# internal_env_board.net
KiCad netlist of a schematic drawn in EAGLE
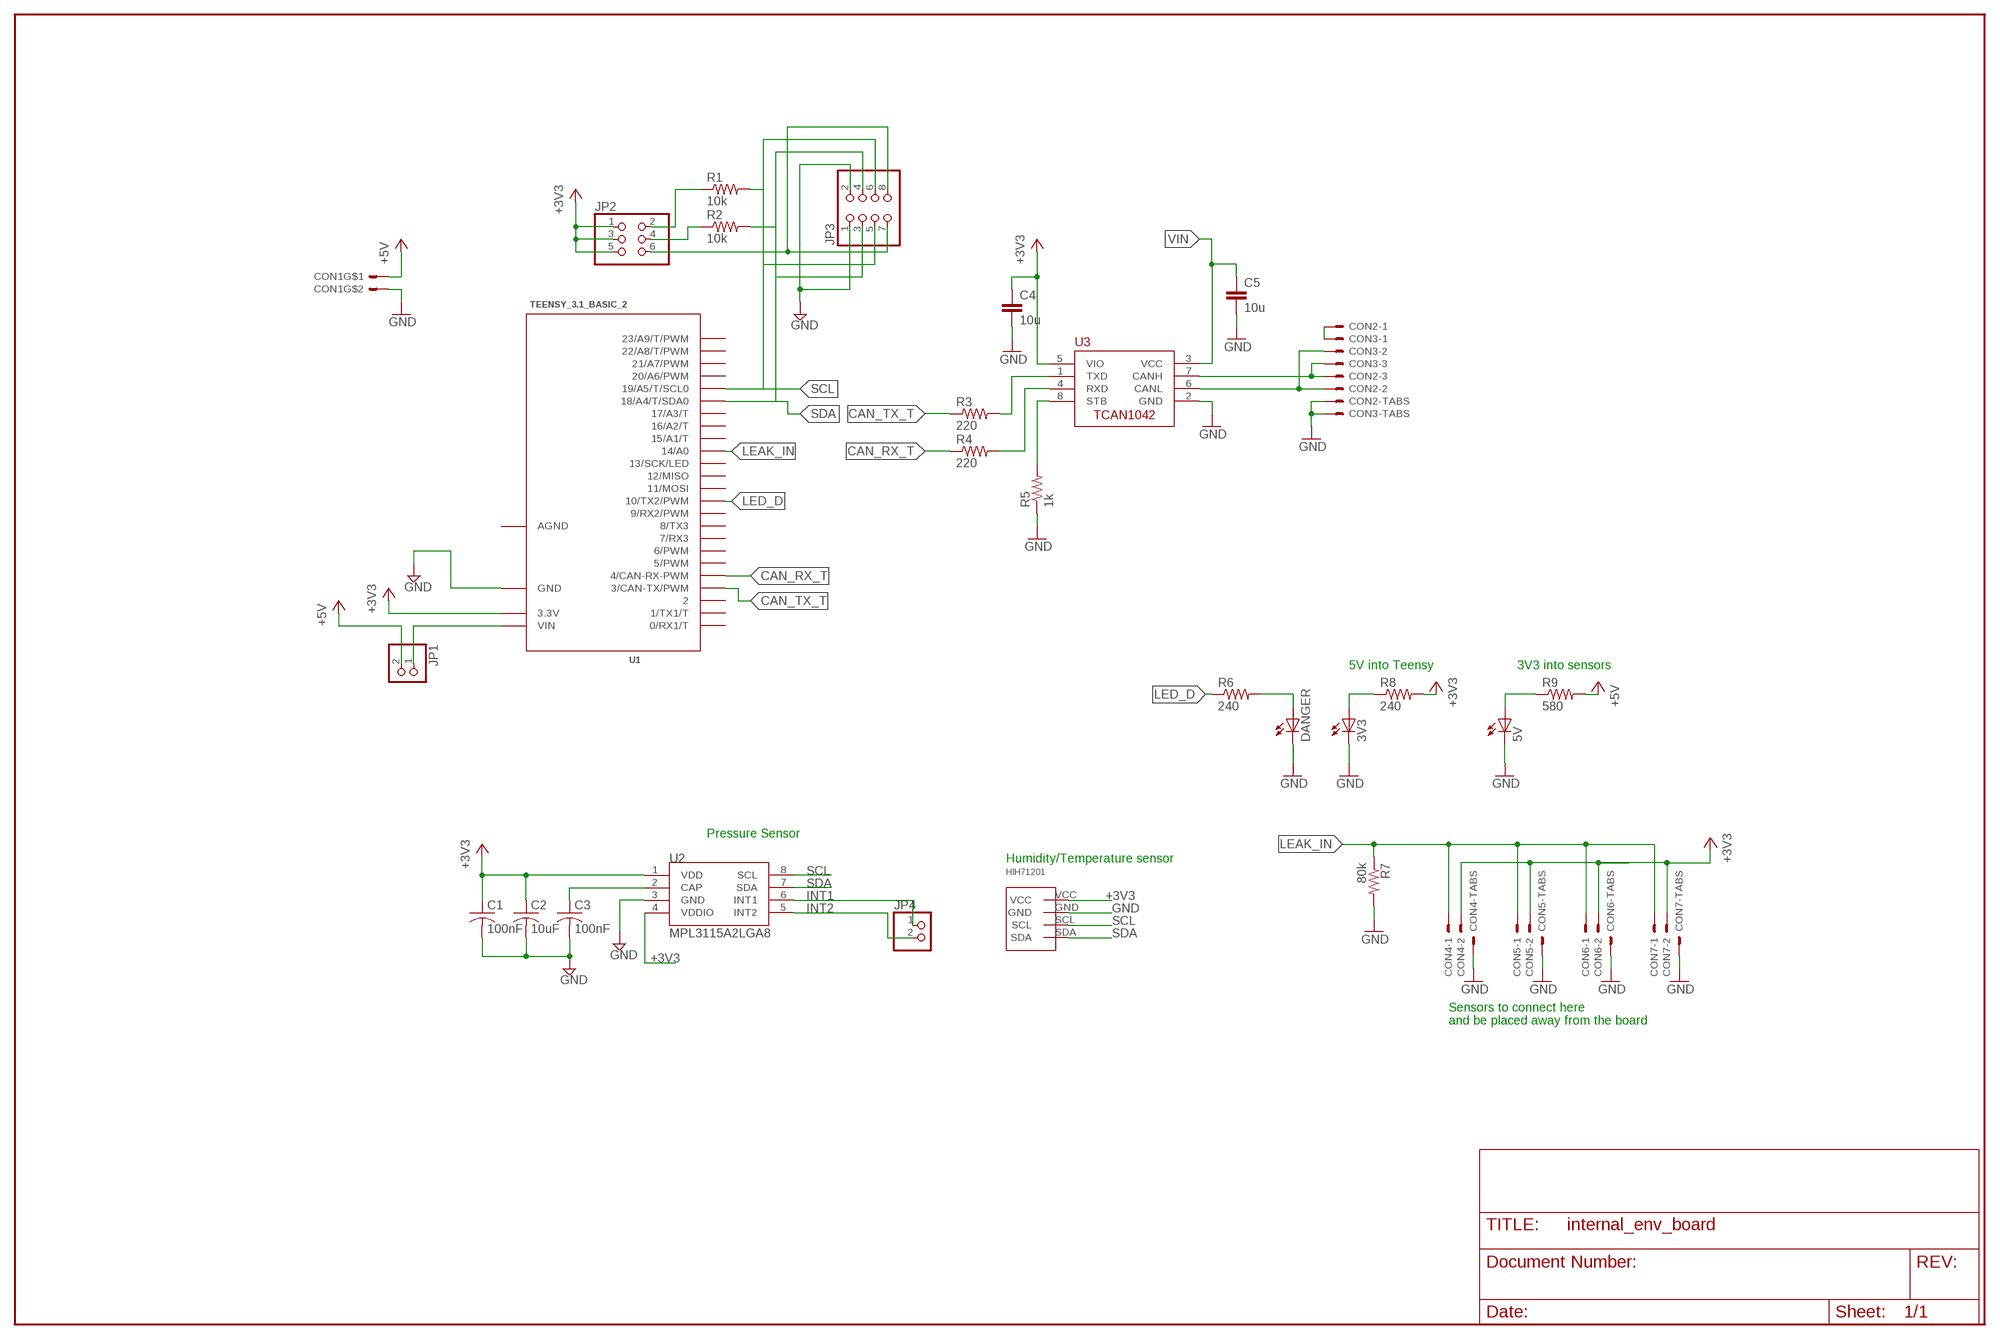
[diagram p0: schematic, sheet 1]

(export (version "E")
  (design (tool "Eeschema 10.0.6"))
  (components
    (comp (ref "3V3")
      (value "LEDSMT1206")
      (footprint "eagle-import:1206")
      (libsource (lib "eagle-import") (part "LEDSMT1206"))
    )
    (comp (ref "5V")
      (value "LEDSMT1206")
      (footprint "eagle-import:1206")
      (libsource (lib "eagle-import") (part "LEDSMT1206"))
    )
    (comp (ref "C1")
      (value "100nF")
      (footprint "eagle-import:C1206")
      (libsource (lib "eagle-import") (part "C-USC1206"))
    )
    (comp (ref "C2")
      (value "10uF")
      (footprint "eagle-import:C1206")
      (libsource (lib "eagle-import") (part "C-USC1206"))
    )
    (comp (ref "C3")
      (value "100nF")
      (footprint "eagle-import:C1206")
      (libsource (lib "eagle-import") (part "C-USC1206"))
    )
    (comp (ref "C4")
      (value "10u")
      (footprint "eagle-import:C0805")
      (libsource (lib "eagle-import") (part "C-EUC0805"))
    )
    (comp (ref "C5")
      (value "10u")
      (footprint "eagle-import:C0805")
      (libsource (lib "eagle-import") (part "C-EUC0805"))
    )
    (comp (ref "CON1")
      (value "MOLEX_5566-2")
      (footprint "eagle-import:5566-2")
      (libsource (lib "eagle-import") (part "MOLEX_5566-2"))
    )
    (comp (ref "CON2")
      (value "SM03B-GHS-TB")
      (footprint "eagle-import:SM03B-GHS-TB")
      (libsource (lib "eagle-import") (part "SM03B-GHS-TB"))
    )
    (comp (ref "CON3")
      (value "SM03B-GHS-TB")
      (footprint "eagle-import:SM03B-GHS-TB")
      (libsource (lib "eagle-import") (part "SM03B-GHS-TB"))
    )
    (comp (ref "CON4")
      (value "SM02B-GHS-TB")
      (footprint "eagle-import:SM02B-GHS-TB")
      (libsource (lib "eagle-import") (part "SM02B-GHS-TB"))
    )
    (comp (ref "CON5")
      (value "SM02B-GHS-TB")
      (footprint "eagle-import:SM02B-GHS-TB")
      (libsource (lib "eagle-import") (part "SM02B-GHS-TB"))
    )
    (comp (ref "CON6")
      (value "SM02B-GHS-TB")
      (footprint "eagle-import:SM02B-GHS-TB")
      (libsource (lib "eagle-import") (part "SM02B-GHS-TB"))
    )
    (comp (ref "CON7")
      (value "SM02B-GHS-TB")
      (footprint "eagle-import:SM02B-GHS-TB")
      (libsource (lib "eagle-import") (part "SM02B-GHS-TB"))
    )
    (comp (ref "DANGER")
      (value "LEDSMT1206")
      (footprint "eagle-import:1206")
      (libsource (lib "eagle-import") (part "LEDSMT1206"))
    )
    (comp (ref "HIH71201")
      (value "HIH7120")
      (footprint "eagle-import:SIP4")
      (libsource (lib "eagle-import") (part "HIH7120"))
    )
    (comp (ref "JP1")
      (value "PINHD-1X2")
      (footprint "eagle-import:1X02")
      (libsource (lib "eagle-import") (part "pinhead_325_PINHD-1X2"))
    )
    (comp (ref "JP2")
      (value "PINHD-2X3")
      (footprint "eagle-import:2X03")
      (libsource (lib "eagle-import") (part "PINHD-2X3"))
    )
    (comp (ref "JP3")
      (value "PINHD-2X4")
      (footprint "eagle-import:2X04")
      (libsource (lib "eagle-import") (part "PINHD-2X4"))
    )
    (comp (ref "JP4")
      (value "PINHD-1X2")
      (footprint "eagle-import:1X02")
      (libsource (lib "eagle-import") (part "PINHD-1X2"))
    )
    (comp (ref "R1")
      (value "10k")
      (footprint "eagle-import:R1206")
      (libsource (lib "eagle-import") (part "R-US_R1206"))
    )
    (comp (ref "R2")
      (value "10k")
      (footprint "eagle-import:R1206")
      (libsource (lib "eagle-import") (part "R-US_R1206"))
    )
    (comp (ref "R3")
      (value "220")
      (footprint "eagle-import:R0805")
      (libsource (lib "eagle-import") (part "R-US_R0805"))
    )
    (comp (ref "R4")
      (value "220")
      (footprint "eagle-import:R0805")
      (libsource (lib "eagle-import") (part "R-US_R0805"))
    )
    (comp (ref "R5")
      (value "1k")
      (footprint "eagle-import:R0805")
      (libsource (lib "eagle-import") (part "R-US_R0805"))
    )
    (comp (ref "R6")
      (value "240")
      (footprint "eagle-import:R1206")
      (libsource (lib "eagle-import") (part "resistor_348_R-US_R1206"))
    )
    (comp (ref "R7")
      (value "80k")
      (footprint "eagle-import:R1206")
      (libsource (lib "eagle-import") (part "resistor_348_R-US_R1206"))
    )
    (comp (ref "R8")
      (value "240")
      (footprint "eagle-import:R1206")
      (libsource (lib "eagle-import") (part "resistor_348_R-US_R1206"))
    )
    (comp (ref "R9")
      (value "580")
      (footprint "eagle-import:R1206")
      (libsource (lib "eagle-import") (part "resistor_348_R-US_R1206"))
    )
    (comp (ref "U1")
      (value "TEENSY_3.1_BASIC_2")
      (footprint "eagle-import:TEENSY_3.1_BASIC_2")
      (libsource (lib "eagle-import") (part "TEENSY_3.1_BASIC_2"))
    )
    (comp (ref "U2")
      (value "MPL3115A2LGA8")
      (footprint "eagle-import:LGA8")
      (libsource (lib "eagle-import") (part "MPL3115A2LGA8"))
    )
    (comp (ref "U3")
      (value "TCAN1042HVDR")
      (footprint "eagle-import:SO-8")
      (libsource (lib "eagle-import") (part "TCAN1042HVDR"))
    )
  )
  (nets
    (net (code "1") (name "+3V3") (class "Default")
      (node (ref "C1") (pin "1") (pinfunction "1_1") (pintype "passive"))
      (node (ref "C2") (pin "1") (pinfunction "1_1") (pintype "passive"))
      (node (ref "C4") (pin "1") (pinfunction "1_1") (pintype "passive"))
      (node (ref "CON4") (pin "P$2") (pinfunction "S_P$2") (pintype "passive"))
      (node (ref "CON5") (pin "P$2") (pinfunction "S_P$2") (pintype "passive"))
      (node (ref "CON6") (pin "P$2") (pinfunction "S_P$2") (pintype "passive"))
      (node (ref "CON7") (pin "P$2") (pinfunction "S_P$2") (pintype "passive"))
      (node (ref "HIH71201") (pin "VCC") (pinfunction "VCC_VCC") (pintype "power_in"))
      (node (ref "JP2") (pin "1") (pinfunction "1_1") (pintype "passive"))
      (node (ref "JP2") (pin "3") (pinfunction "3_3") (pintype "passive"))
      (node (ref "JP2") (pin "5") (pinfunction "5_5") (pintype "passive"))
      (node (ref "R8") (pin "2") (pinfunction "2_2") (pintype "passive"))
      (node (ref "U1") (pin "3.3V") (pinfunction "3.3V_3.3V") (pintype "power_in"))
      (node (ref "U2") (pin "1") (pinfunction "VDD_1") (pintype "bidirectional"))
      (node (ref "U2") (pin "4") (pinfunction "VDDIO_4") (pintype "bidirectional"))
      (node (ref "U3") (pin "5") (pinfunction "VIO_5") (pintype "bidirectional"))
    )
    (net (code "2") (name "+5V") (class "Default")
      (node (ref "CON1") (pin "1") (pinfunction "S_1") (pintype "passive"))
      (node (ref "JP1") (pin "2") (pinfunction "2_2") (pintype "passive"))
      (node (ref "R9") (pin "2") (pinfunction "2_2") (pintype "passive"))
    )
    (net (code "3") (name "/AGND") (class "Default")
      (node (ref "U1") (pin "AGND") (pinfunction "AGND_AGND") (pintype "power_in"))
    )
    (net (code "4") (name "/INT1") (class "Default")
      (node (ref "JP4") (pin "1") (pinfunction "1_1") (pintype "passive"))
      (node (ref "U2") (pin "6") (pinfunction "INT1_6") (pintype "bidirectional"))
    )
    (net (code "5") (name "/INT2") (class "Default")
      (node (ref "JP4") (pin "2") (pinfunction "2_2") (pintype "passive"))
      (node (ref "U2") (pin "5") (pinfunction "INT2_5") (pintype "bidirectional"))
    )
    (net (code "6") (name "CAN_RX_T") (class "Default")
      (node (ref "R4") (pin "1") (pinfunction "1_1") (pintype "passive"))
      (node (ref "U1") (pin "4") (pinfunction "4/CAN-RX-PWM_4") (pintype "bidirectional"))
    )
    (net (code "7") (name "CAN_TX_T") (class "Default")
      (node (ref "R3") (pin "1") (pinfunction "1_1") (pintype "passive"))
      (node (ref "U1") (pin "3") (pinfunction "3/CAN-TX/PWM_3") (pintype "bidirectional"))
    )
    (net (code "8") (name "GND") (class "Default")
      (node (ref "3V3") (pin "C") (pinfunction "C_C") (pintype "passive"))
      (node (ref "5V") (pin "C") (pinfunction "C_C") (pintype "passive"))
      (node (ref "C1") (pin "2") (pinfunction "2_2") (pintype "passive"))
      (node (ref "C2") (pin "2") (pinfunction "2_2") (pintype "passive"))
      (node (ref "C3") (pin "2") (pinfunction "2_2") (pintype "passive"))
      (node (ref "C4") (pin "2") (pinfunction "2_2") (pintype "passive"))
      (node (ref "C5") (pin "2") (pinfunction "2_2") (pintype "passive"))
      (node (ref "CON1") (pin "2") (pinfunction "S_2") (pintype "passive"))
      (node (ref "CON2") (pin "P$4") (pinfunction "S_P$4") (pintype "passive"))
      (node (ref "CON2") (pin "P$5") (pinfunction "S_P$5") (pintype "passive"))
      (node (ref "CON3") (pin "P$4") (pinfunction "S_P$4") (pintype "passive"))
      (node (ref "CON3") (pin "P$5") (pinfunction "S_P$5") (pintype "passive"))
      (node (ref "CON4") (pin "P$3") (pinfunction "S_P$3") (pintype "passive"))
      (node (ref "CON4") (pin "P$4") (pinfunction "S_P$4") (pintype "passive"))
      (node (ref "CON5") (pin "P$3") (pinfunction "S_P$3") (pintype "passive"))
      (node (ref "CON5") (pin "P$4") (pinfunction "S_P$4") (pintype "passive"))
      (node (ref "CON6") (pin "P$3") (pinfunction "S_P$3") (pintype "passive"))
      (node (ref "CON6") (pin "P$4") (pinfunction "S_P$4") (pintype "passive"))
      (node (ref "CON7") (pin "P$3") (pinfunction "S_P$3") (pintype "passive"))
      (node (ref "CON7") (pin "P$4") (pinfunction "S_P$4") (pintype "passive"))
      (node (ref "DANGER") (pin "C") (pinfunction "C_C") (pintype "passive"))
      (node (ref "HIH71201") (pin "GND") (pinfunction "GND_GND") (pintype "power_in"))
      (node (ref "JP3") (pin "1") (pinfunction "1_1") (pintype "passive"))
      (node (ref "JP3") (pin "2") (pinfunction "2_2") (pintype "passive"))
      (node (ref "R5") (pin "1") (pinfunction "1_1") (pintype "passive"))
      (node (ref "R7") (pin "2") (pinfunction "2_2") (pintype "passive"))
      (node (ref "U1") (pin "GND") (pinfunction "GND_GND") (pintype "power_in"))
      (node (ref "U2") (pin "3") (pinfunction "GND_3") (pintype "bidirectional"))
      (node (ref "U3") (pin "2") (pinfunction "GND_2") (pintype "bidirectional"))
    )
    (net (code "9") (name "LEAK_IN") (class "Default")
      (node (ref "CON4") (pin "P$1") (pinfunction "S_P$1") (pintype "passive"))
      (node (ref "CON5") (pin "P$1") (pinfunction "S_P$1") (pintype "passive"))
      (node (ref "CON6") (pin "P$1") (pinfunction "S_P$1") (pintype "passive"))
      (node (ref "CON7") (pin "P$1") (pinfunction "S_P$1") (pintype "passive"))
      (node (ref "R7") (pin "1") (pinfunction "1_1") (pintype "passive"))
      (node (ref "U1") (pin "14/A0") (pinfunction "14/A0_14/A0") (pintype "bidirectional"))
    )
    (net (code "10") (name "LED_D") (class "Default")
      (node (ref "R6") (pin "1") (pinfunction "1_1") (pintype "passive"))
      (node (ref "U1") (pin "10") (pinfunction "10/TX2/PWM_10") (pintype "bidirectional"))
    )
    (net (code "11") (name "Net-(3V3-PadA)") (class "Default")
      (node (ref "3V3") (pin "A") (pinfunction "A_A") (pintype "passive"))
      (node (ref "R8") (pin "1") (pinfunction "1_1") (pintype "passive"))
    )
    (net (code "12") (name "Net-(5V-PadA)") (class "Default")
      (node (ref "5V") (pin "A") (pinfunction "A_A") (pintype "passive"))
      (node (ref "R9") (pin "1") (pinfunction "1_1") (pintype "passive"))
    )
    (net (code "13") (name "Net-(CON2A-S)") (class "Default")
      (node (ref "CON2") (pin "P$1") (pinfunction "S_P$1") (pintype "passive"))
      (node (ref "CON3") (pin "P$1") (pinfunction "S_P$1") (pintype "passive"))
    )
    (net (code "14") (name "Net-(CON2B-S)") (class "Default")
      (node (ref "CON2") (pin "P$2") (pinfunction "S_P$2") (pintype "passive"))
      (node (ref "CON3") (pin "P$2") (pinfunction "S_P$2") (pintype "passive"))
      (node (ref "U3") (pin "6") (pinfunction "CANL_6") (pintype "bidirectional"))
    )
    (net (code "15") (name "Net-(CON2C-S)") (class "Default")
      (node (ref "CON2") (pin "P$3") (pinfunction "S_P$3") (pintype "passive"))
      (node (ref "CON3") (pin "P$3") (pinfunction "S_P$3") (pintype "passive"))
      (node (ref "U3") (pin "7") (pinfunction "CANH_7") (pintype "bidirectional"))
    )
    (net (code "16") (name "Net-(DANGER-PadA)") (class "Default")
      (node (ref "DANGER") (pin "A") (pinfunction "A_A") (pintype "passive"))
      (node (ref "R6") (pin "2") (pinfunction "2_2") (pintype "passive"))
    )
    (net (code "17") (name "Net-(JP2-Pad2)") (class "Default")
      (node (ref "JP2") (pin "2") (pinfunction "2_2") (pintype "passive"))
      (node (ref "R1") (pin "1") (pinfunction "1_1") (pintype "passive"))
    )
    (net (code "18") (name "Net-(JP2-Pad4)") (class "Default")
      (node (ref "JP2") (pin "4") (pinfunction "4_4") (pintype "passive"))
      (node (ref "R2") (pin "1") (pinfunction "1_1") (pintype "passive"))
    )
    (net (code "19") (name "Net-(JP2-Pad6)") (class "Default")
      (node (ref "JP2") (pin "6") (pinfunction "6_6") (pintype "passive"))
      (node (ref "JP3") (pin "7") (pinfunction "7_7") (pintype "passive"))
      (node (ref "JP3") (pin "8") (pinfunction "8_8") (pintype "passive"))
    )
    (net (code "20") (name "Net-(U2-CAP)") (class "Default")
      (node (ref "C3") (pin "1") (pinfunction "1_1") (pintype "passive"))
      (node (ref "U2") (pin "2") (pinfunction "CAP_2") (pintype "bidirectional"))
    )
    (net (code "21") (name "Net-(U3-RXD)") (class "Default")
      (node (ref "R4") (pin "2") (pinfunction "2_2") (pintype "passive"))
      (node (ref "U3") (pin "4") (pinfunction "RXD_4") (pintype "bidirectional"))
    )
    (net (code "22") (name "Net-(U3-STB)") (class "Default")
      (node (ref "R5") (pin "2") (pinfunction "2_2") (pintype "passive"))
      (node (ref "U3") (pin "8") (pinfunction "STB_8") (pintype "bidirectional"))
    )
    (net (code "23") (name "Net-(U3-TXD)") (class "Default")
      (node (ref "R3") (pin "2") (pinfunction "2_2") (pintype "passive"))
      (node (ref "U3") (pin "1") (pinfunction "TXD_1") (pintype "bidirectional"))
    )
    (net (code "24") (name "SCL") (class "Default")
      (node (ref "HIH71201") (pin "SCL") (pinfunction "SCL_SCL") (pintype "bidirectional"))
      (node (ref "JP3") (pin "5") (pinfunction "5_5") (pintype "passive"))
      (node (ref "JP3") (pin "6") (pinfunction "6_6") (pintype "passive"))
      (node (ref "R1") (pin "2") (pinfunction "2_2") (pintype "passive"))
      (node (ref "U1") (pin "19/A5") (pinfunction "19/A5/T/SCL0_19/A5") (pintype "bidirectional"))
      (node (ref "U2") (pin "8") (pinfunction "SCL_8") (pintype "bidirectional"))
    )
    (net (code "25") (name "SDA") (class "Default")
      (node (ref "HIH71201") (pin "SDA") (pinfunction "SDA_SDA") (pintype "bidirectional"))
      (node (ref "JP3") (pin "3") (pinfunction "3_3") (pintype "passive"))
      (node (ref "JP3") (pin "4") (pinfunction "4_4") (pintype "passive"))
      (node (ref "R2") (pin "2") (pinfunction "2_2") (pintype "passive"))
      (node (ref "U1") (pin "18/A4") (pinfunction "18/A4/T/SDA0_18/A4") (pintype "bidirectional"))
      (node (ref "U2") (pin "7") (pinfunction "SDA_7") (pintype "bidirectional"))
    )
    (net (code "26") (name "VIN") (class "Default")
      (node (ref "C5") (pin "1") (pinfunction "1_1") (pintype "passive"))
      (node (ref "JP1") (pin "1") (pinfunction "1_1") (pintype "passive"))
      (node (ref "U1") (pin "VIN") (pinfunction "VIN_VIN") (pintype "power_in"))
      (node (ref "U3") (pin "3") (pinfunction "VCC_3") (pintype "bidirectional"))
    )
    (net (code "27") (name "unconnected-(U1-0{slash}RX1{slash}T-Pad0)") (class "Default")
      (node (ref "U1") (pin "0") (pinfunction "0/RX1/T_0") (pintype "bidirectional"))
    )
    (net (code "28") (name "unconnected-(U1-1{slash}TX1{slash}T-Pad1)") (class "Default")
      (node (ref "U1") (pin "1") (pinfunction "1/TX1/T_1") (pintype "bidirectional"))
    )
    (net (code "29") (name "unconnected-(U1-5{slash}PWM-Pad5)") (class "Default")
      (node (ref "U1") (pin "5") (pinfunction "5/PWM_5") (pintype "bidirectional"))
    )
    (net (code "30") (name "unconnected-(U1-6{slash}PWM-Pad6)") (class "Default")
      (node (ref "U1") (pin "6") (pinfunction "6/PWM_6") (pintype "bidirectional"))
    )
    (net (code "31") (name "unconnected-(U1-7{slash}RX3-Pad7)") (class "Default")
      (node (ref "U1") (pin "7") (pinfunction "7/RX3_7") (pintype "bidirectional"))
    )
    (net (code "32") (name "unconnected-(U1-8{slash}TX3-Pad8)") (class "Default")
      (node (ref "U1") (pin "8") (pinfunction "8/TX3_8") (pintype "bidirectional"))
    )
    (net (code "33") (name "unconnected-(U1-9{slash}RX2{slash}PWM-Pad9)") (class "Default")
      (node (ref "U1") (pin "9") (pinfunction "9/RX2/PWM_9") (pintype "bidirectional"))
    )
    (net (code "34") (name "unconnected-(U1-11{slash}MOSI-Pad11)") (class "Default")
      (node (ref "U1") (pin "11") (pinfunction "11/MOSI_11") (pintype "bidirectional"))
    )
    (net (code "35") (name "unconnected-(U1-12{slash}MISO-Pad12)") (class "Default")
      (node (ref "U1") (pin "12") (pinfunction "12/MISO_12") (pintype "bidirectional"))
    )
    (net (code "36") (name "unconnected-(U1-13{slash}SCK{slash}LED-Pad13)") (class "Default")
      (node (ref "U1") (pin "13") (pinfunction "13/SCK/LED_13") (pintype "bidirectional"))
    )
    (net (code "37") (name "unconnected-(U1-15{slash}A1{slash}T-Pad15{slash}A1)") (class "Default")
      (node (ref "U1") (pin "15/A1") (pinfunction "15/A1/T_15/A1") (pintype "bidirectional"))
    )
    (net (code "38") (name "unconnected-(U1-16{slash}A2{slash}T-Pad16{slash}A2)") (class "Default")
      (node (ref "U1") (pin "16/A2") (pinfunction "16/A2/T_16/A2") (pintype "bidirectional"))
    )
    (net (code "39") (name "unconnected-(U1-17{slash}A3{slash}T-Pad17{slash}A3)") (class "Default")
      (node (ref "U1") (pin "17/A3") (pinfunction "17/A3/T_17/A3") (pintype "bidirectional"))
    )
    (net (code "40") (name "unconnected-(U1-20{slash}A6{slash}PWM-Pad20{slash}A6)") (class "Default")
      (node (ref "U1") (pin "20/A6") (pinfunction "20/A6/PWM_20/A6") (pintype "bidirectional"))
    )
    (net (code "41") (name "unconnected-(U1-21{slash}A7{slash}PWM-Pad21{slash}A7)") (class "Default")
      (node (ref "U1") (pin "21/A7") (pinfunction "21/A7/PWM_21/A7") (pintype "bidirectional"))
    )
    (net (code "42") (name "unconnected-(U1-22{slash}A8{slash}T{slash}PWM-Pad22{slash}A8)") (class "Default")
      (node (ref "U1") (pin "22/A8") (pinfunction "22/A8/T/PWM_22/A8") (pintype "bidirectional"))
    )
    (net (code "43") (name "unconnected-(U1-23{slash}A9{slash}T{slash}PWM-Pad23{slash}A9)") (class "Default")
      (node (ref "U1") (pin "23/A9") (pinfunction "23/A9/T/PWM_23/A9") (pintype "bidirectional"))
    )
    (net (code "44") (name "unconnected-(U1-Pad2)") (class "Default")
      (node (ref "U1") (pin "2") (pinfunction "2_2") (pintype "bidirectional"))
    )
  )
)
